# icamlamp_evo.net
KiCad netlist of a schematic drawn in Altium Designer
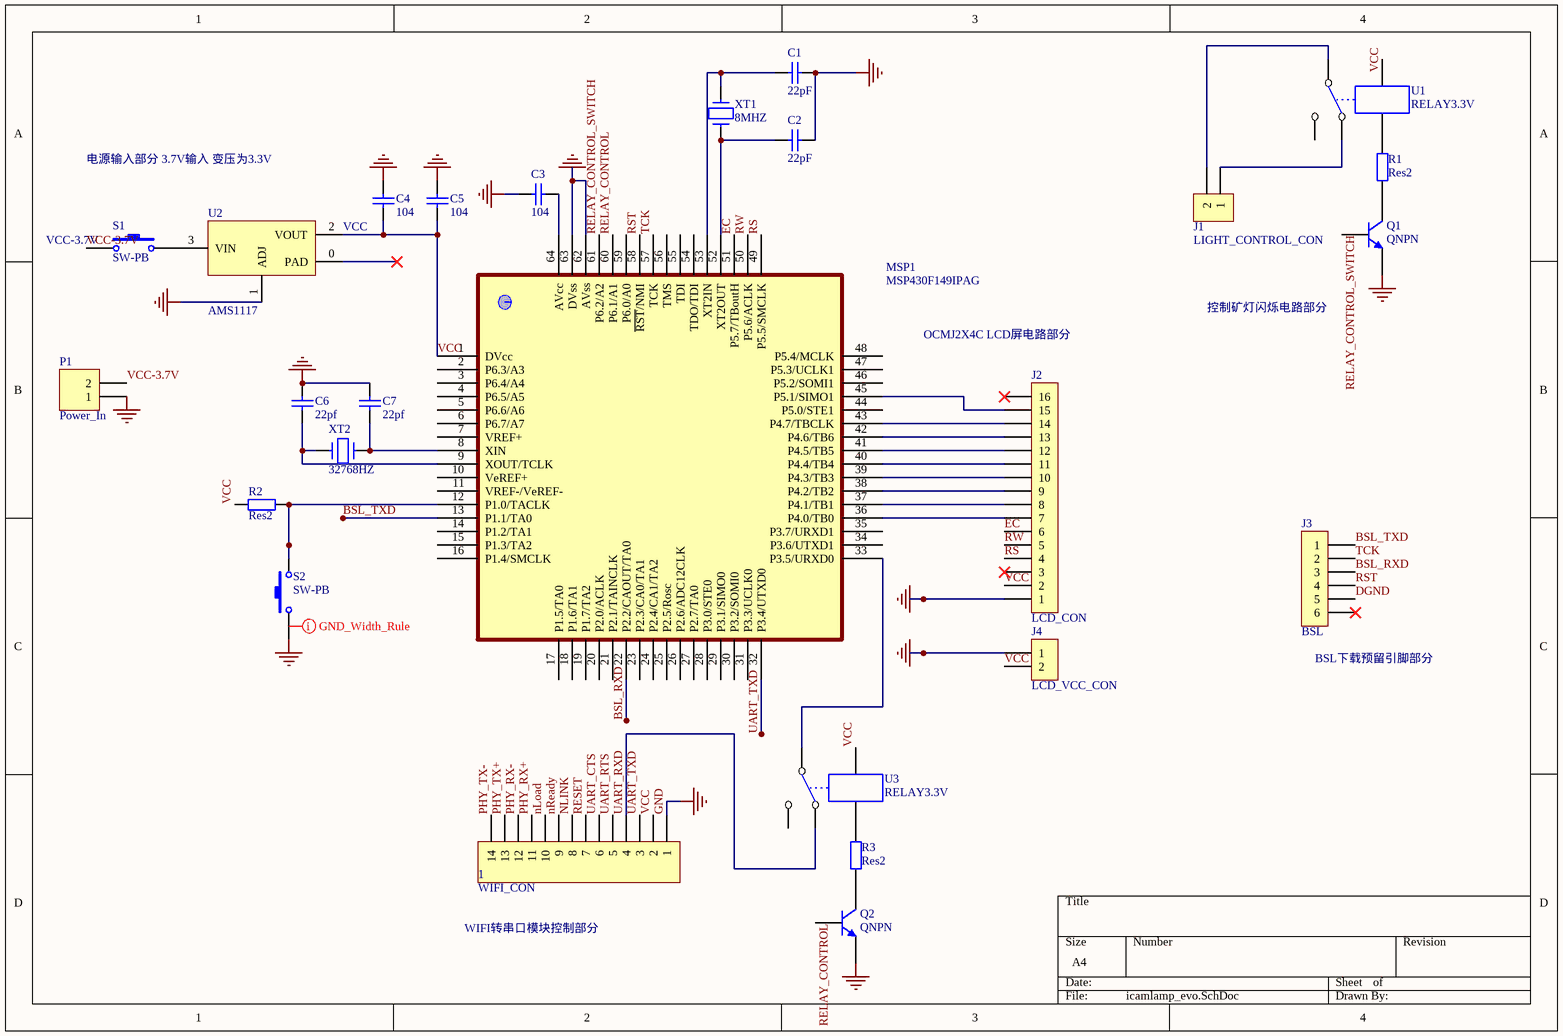
[diagram p0: icamlamp_evo.SchDoc]

(export (version "E")
  (design (tool "Eeschema 10.0.6"))
  (components
    (comp (ref "1") (value "WIFI_CON") (footprint "wificon") (libsource (lib "常用元件库") (part "CON14")))
    (comp (ref "C1")
      (value "22pF")
      (footprint "0805")
      (description "Capacitor")
      (fields (field (name "PUBLISHER") "Altium Limited"))
      (libsource (lib "Miscellaneous Devices") (part "Cap"))
    )
    (comp (ref "C2")
      (value "22pF")
      (footprint "0805")
      (description "Capacitor")
      (fields (field (name "PUBLISHER") "Altium Limited"))
      (libsource (lib "Miscellaneous Devices") (part "Cap"))
    )
    (comp (ref "C3")
      (value "104")
      (footprint "0805")
      (description "Capacitor")
      (fields (field (name "PUBLISHER") "Altium Limited"))
      (libsource (lib "Miscellaneous Devices") (part "Cap"))
    )
    (comp (ref "C4")
      (value "104")
      (footprint "封装库:0805")
      (description "Capacitor")
      (fields (field (name "PUBLISHER") "Altium Limited"))
      (libsource (lib "Miscellaneous Devices") (part "Cap"))
    )
    (comp (ref "C5")
      (value "104")
      (footprint "0805")
      (description "Capacitor")
      (fields (field (name "PUBLISHER") "Altium Limited"))
      (libsource (lib "Miscellaneous Devices") (part "Cap"))
    )
    (comp (ref "C6")
      (value "22pf")
      (footprint "0805")
      (description "Capacitor")
      (fields (field (name "PUBLISHER") "Altium Limited"))
      (libsource (lib "Miscellaneous Devices") (part "Cap"))
    )
    (comp (ref "C7")
      (value "22pf")
      (footprint "0805")
      (description "Capacitor")
      (fields (field (name "PUBLISHER") "Altium Limited"))
      (libsource (lib "Miscellaneous Devices") (part "Cap"))
    )
    (comp (ref "J1") (value "LIGHT_CONTROL_CON") (footprint "SIP2") (libsource (lib "") (part "CON2_1")))
    (comp (ref "J2") (value "LCD_CON") (footprint "HDR2X8") (libsource (lib "元件库") (part "CON16")))
    (comp (ref "J3") (value "BSL") (footprint "HDR2X3") (libsource (lib "常用元件库") (part "CON6")))
    (comp (ref "J4") (value "LCD_VCC_CON") (footprint "SIP2") (libsource (lib "常用元件库") (part "CON2")))
    (comp (ref "MSP1")
      (value "MSP430F149IPAG")
      (footprint "PAG")
      (libsource (lib "MSP430SCH") (part "MSP430F149IPAG"))
    )
    (comp (ref "P1")
      (value "Power_In")
      (footprint "HDR1X2H")
      (description "Header, 2-Pin, Right Angle")
      (fields (field (name "PUBLISHER") "Altium Limited"))
      (libsource (lib "Miscellaneous Connectors") (part "Header 2H"))
    )
    (comp (ref "Q1")
      (value "QNPN")
      (footprint "SO-G3/C2.5")
      (description "NPN Bipolar Transistor")
      (fields (field (name "PUBLISHER") "Altium Limited"))
      (libsource (lib "Miscellaneous Devices") (part "QNPN"))
    )
    (comp (ref "Q2")
      (value "QNPN")
      (footprint "SO-G3/C2.5")
      (description "NPN Bipolar Transistor")
      (fields (field (name "PUBLISHER") "Altium Limited"))
      (libsource (lib "Miscellaneous Devices") (part "QNPN"))
    )
    (comp (ref "R1")
      (value "Res2")
      (footprint "封装库:0805")
      (description "Resistor")
      (fields (field (name "PUBLISHER") "Altium Limited"))
      (libsource (lib "") (part "Res2_1"))
    )
    (comp (ref "R2")
      (value "Res2")
      (footprint "0805")
      (description "Resistor")
      (fields (field (name "PUBLISHER") "Altium Limited"))
      (libsource (lib "Miscellaneous Devices") (part "Res2"))
    )
    (comp (ref "R3")
      (value "Res2")
      (footprint "封装库:0805")
      (description "Resistor")
      (fields (field (name "PUBLISHER") "Altium Limited"))
      (libsource (lib "") (part "Res2_1"))
    )
    (comp (ref "S1")
      (value "SW-PB")
      (footprint "SPST-2")
      (description "Switch")
      (fields (field (name "PUBLISHER") "Altium Limited"))
      (libsource (lib "Miscellaneous Devices") (part "SW-PB"))
    )
    (comp (ref "S2")
      (value "SW-PB")
      (footprint "SPST-2")
      (description "Switch")
      (fields (field (name "PUBLISHER") "Altium Limited"))
      (libsource (lib "Miscellaneous Devices") (part "SW-PB"))
    )
    (comp (ref "U1") (value "RELAY3.3V") (footprint "Relay5V") (libsource (lib "继电器类元件") (part "RELAY5V")))
    (comp (ref "U2")
      (value "AMS1117")
      (footprint "SOT-223")
      (description "LDO ADJ")
      (libsource (lib "元件库") (part "AMS1117"))
    )
    (comp (ref "U3") (value "RELAY3.3V") (footprint "Relay5V") (libsource (lib "继电器类元件") (part "RELAY5V")))
    (comp (ref "XT1")
      (value "8MHZ")
      (footprint "HC-49S")
      (description "CY-49S-8MHZ")
      (libsource (lib "晶振") (part "8MHZ"))
    )
    (comp (ref "XT2")
      (value "32768HZ")
      (footprint "AT26")
      (description "CY-AT26-32768HZ")
      (libsource (lib "晶振") (part "32768HZ"))
    )
  )
  (nets
    (net (code "1") (name "/BSL_RXD") (class "Default")
      (node (ref "J3") (pin "3") (pinfunction "3_3") (pintype "passive"))
      (node (ref "MSP1") (pin "22") (pinfunction "P2.2/CAOUT/TA0_22") (pintype "passive"))
    )
    (net (code "2") (name "/BSL_TXD") (class "Default")
      (node (ref "J3") (pin "1") (pinfunction "1_1") (pintype "passive"))
      (node (ref "MSP1") (pin "13") (pinfunction "P1.1/TA0_13") (pintype "passive"))
    )
    (net (code "3") (name "/DGND") (class "Default")
      (node (ref "J3") (pin "5") (pinfunction "5_5") (pintype "passive"))
    )
    (net (code "4") (name "/EC") (class "Default")
      (node (ref "J2") (pin "6") (pinfunction "6_6") (pintype "passive"))
      (node (ref "MSP1") (pin "51") (pinfunction "P5.7/TBoutH_51") (pintype "passive"))
    )
    (net (code "5") (name "/NLINK") (class "Default")
      (node (ref "1") (pin "8") (pinfunction "8_8") (pintype "passive"))
    )
    (net (code "6") (name "/PHY_RX+") (class "Default")
      (node (ref "1") (pin "11") (pinfunction "11_11") (pintype "passive"))
    )
    (net (code "7") (name "/PHY_RX-") (class "Default")
      (node (ref "1") (pin "12") (pinfunction "12_12") (pintype "passive"))
    )
    (net (code "8") (name "/PHY_TX+") (class "Default")
      (node (ref "1") (pin "13") (pinfunction "13_13") (pintype "passive"))
    )
    (net (code "9") (name "/PHY_TX-") (class "Default")
      (node (ref "1") (pin "14") (pinfunction "14_14") (pintype "passive"))
    )
    (net (code "10") (name "/RELAY_CONTROL") (class "Default")
      (node (ref "MSP1") (pin "60") (pinfunction "P6.1/A1_60") (pintype "passive"))
      (node (ref "Q2") (pin "2") (pinfunction "B_2") (pintype "passive"))
    )
    (net (code "11") (name "/RELAY_CONTROL_SWITCH") (class "Default")
      (node (ref "MSP1") (pin "61") (pinfunction "P6.2/A2_61") (pintype "passive"))
      (node (ref "Q1") (pin "2") (pinfunction "B_2") (pintype "passive"))
    )
    (net (code "12") (name "/RESET") (class "Default")
      (node (ref "1") (pin "7") (pinfunction "7_7") (pintype "passive"))
    )
    (net (code "13") (name "/RS") (class "Default")
      (node (ref "J2") (pin "4") (pinfunction "4_4") (pintype "passive"))
      (node (ref "MSP1") (pin "49") (pinfunction "P5.5/SMCLK_49") (pintype "passive"))
    )
    (net (code "14") (name "/RST") (class "Default")
      (node (ref "J3") (pin "4") (pinfunction "4_4") (pintype "passive"))
      (node (ref "MSP1") (pin "58") (pinfunction "~{RST}/NMI_58") (pintype "passive"))
    )
    (net (code "15") (name "/RW") (class "Default")
      (node (ref "J2") (pin "5") (pinfunction "5_5") (pintype "passive"))
      (node (ref "MSP1") (pin "50") (pinfunction "P5.6/ACLK_50") (pintype "passive"))
    )
    (net (code "16") (name "/TCK") (class "Default")
      (node (ref "J3") (pin "2") (pinfunction "2_2") (pintype "passive"))
      (node (ref "MSP1") (pin "57") (pinfunction "TCK_57") (pintype "passive"))
    )
    (net (code "17") (name "/UART_CTS") (class "Default")
      (node (ref "1") (pin "6") (pinfunction "6_6") (pintype "passive"))
    )
    (net (code "18") (name "/UART_RTS") (class "Default")
      (node (ref "1") (pin "5") (pinfunction "5_5") (pintype "passive"))
    )
    (net (code "19") (name "/UART_RXD") (class "Default")
      (node (ref "1") (pin "4") (pinfunction "4_4") (pintype "passive"))
      (node (ref "U3") (pin "3") (pinfunction "3_3") (pintype "passive"))
    )
    (net (code "20") (name "/UART_TXD") (class "Default")
      (node (ref "1") (pin "3") (pinfunction "3_3") (pintype "passive"))
      (node (ref "MSP1") (pin "32") (pinfunction "P3.4/UTXD0_32") (pintype "passive"))
    )
    (net (code "21") (name "/VCC") (class "Default")
      (node (ref "1") (pin "2") (pinfunction "2_2") (pintype "passive"))
      (node (ref "C4") (pin "2") (pinfunction "2_2") (pintype "passive"))
      (node (ref "C5") (pin "2") (pinfunction "2_2") (pintype "passive"))
      (node (ref "J2") (pin "2") (pinfunction "2_2") (pintype "passive"))
      (node (ref "J4") (pin "2") (pinfunction "2_2") (pintype "passive"))
      (node (ref "MSP1") (pin "1") (pinfunction "DVcc_1") (pintype "passive"))
      (node (ref "R2") (pin "1") (pinfunction "1_1") (pintype "passive"))
      (node (ref "U2") (pin "2") (pinfunction "VOUT_2") (pintype "passive"))
      (node (ref "U3") (pin "4") (pinfunction "4_4") (pintype "passive"))
    )
    (net (code "22") (name "/VCC-3.7V") (class "Default")
      (node (ref "P1") (pin "2") (pinfunction "2_2") (pintype "passive"))
      (node (ref "S1") (pin "1") (pinfunction "1_1") (pintype "passive"))
    )
    (net (code "23") (name "/nLoad") (class "Default")
      (node (ref "1") (pin "10") (pinfunction "10_10") (pintype "passive"))
    )
    (net (code "24") (name "/nReady") (class "Default")
      (node (ref "1") (pin "9") (pinfunction "9_9") (pintype "passive"))
    )
    (net (code "25") (name "GND") (class "Default")
      (node (ref "1") (pin "1") (pinfunction "1_1") (pintype "passive"))
      (node (ref "C1") (pin "1") (pinfunction "1_1") (pintype "passive"))
      (node (ref "C2") (pin "1") (pinfunction "1_1") (pintype "passive"))
      (node (ref "C3") (pin "2") (pinfunction "2_2") (pintype "passive"))
      (node (ref "C4") (pin "1") (pinfunction "1_1") (pintype "passive"))
      (node (ref "C5") (pin "1") (pinfunction "1_1") (pintype "passive"))
      (node (ref "C6") (pin "2") (pinfunction "2_2") (pintype "passive"))
      (node (ref "C7") (pin "2") (pinfunction "2_2") (pintype "passive"))
      (node (ref "J2") (pin "1") (pinfunction "1_1") (pintype "passive"))
      (node (ref "J4") (pin "1") (pinfunction "1_1") (pintype "passive"))
      (node (ref "MSP1") (pin "62") (pinfunction "AVss_62") (pintype "passive"))
      (node (ref "MSP1") (pin "63") (pinfunction "DVss_63") (pintype "passive"))
      (node (ref "P1") (pin "1") (pinfunction "1_1") (pintype "passive"))
      (node (ref "Q1") (pin "3") (pinfunction "E_3") (pintype "passive"))
      (node (ref "Q2") (pin "3") (pinfunction "E_3") (pintype "passive"))
      (node (ref "S2") (pin "1") (pinfunction "1_1") (pintype "passive"))
      (node (ref "U2") (pin "1") (pinfunction "ADJ_1") (pintype "passive"))
    )
    (net (code "26") (name "Net-(J1-Pad1)") (class "Default")
      (node (ref "J1") (pin "1") (pinfunction "1_1") (pintype "passive"))
      (node (ref "U1") (pin "3") (pinfunction "3_3") (pintype "passive"))
    )
    (net (code "27") (name "Net-(J1-Pad2)") (class "Default")
      (node (ref "J1") (pin "2") (pinfunction "2_2") (pintype "passive"))
      (node (ref "U1") (pin "1") (pinfunction "1_1") (pintype "passive"))
    )
    (net (code "28") (name "Net-(MSP1-AVcc)") (class "Default")
      (node (ref "C3") (pin "1") (pinfunction "1_1") (pintype "passive"))
      (node (ref "MSP1") (pin "64") (pinfunction "AVcc_64") (pintype "passive"))
    )
    (net (code "29") (name "Net-(MSP1-P1.0{slash}TACLK)") (class "Default")
      (node (ref "MSP1") (pin "12") (pinfunction "P1.0/TACLK_12") (pintype "passive"))
      (node (ref "R2") (pin "2") (pinfunction "2_2") (pintype "passive"))
      (node (ref "S2") (pin "2") (pinfunction "2_2") (pintype "passive"))
    )
    (net (code "30") (name "Net-(MSP1-P3.5{slash}URXD0)") (class "Default")
      (node (ref "MSP1") (pin "33") (pinfunction "P3.5/URXD0_33") (pintype "passive"))
      (node (ref "U3") (pin "1") (pinfunction "1_1") (pintype "passive"))
    )
    (net (code "31") (name "Net-(MSP1-P4.0{slash}TB0)") (class "Default")
      (node (ref "J2") (pin "7") (pinfunction "7_7") (pintype "passive"))
      (node (ref "MSP1") (pin "36") (pinfunction "P4.0/TB0_36") (pintype "passive"))
    )
    (net (code "32") (name "Net-(MSP1-P4.1{slash}TB1)") (class "Default")
      (node (ref "J2") (pin "8") (pinfunction "8_8") (pintype "passive"))
      (node (ref "MSP1") (pin "37") (pinfunction "P4.1/TB1_37") (pintype "passive"))
    )
    (net (code "33") (name "Net-(MSP1-P4.2{slash}TB2)") (class "Default")
      (node (ref "J2") (pin "9") (pinfunction "9_9") (pintype "passive"))
      (node (ref "MSP1") (pin "38") (pinfunction "P4.2/TB2_38") (pintype "passive"))
    )
    (net (code "34") (name "Net-(MSP1-P4.3{slash}TB3)") (class "Default")
      (node (ref "J2") (pin "10") (pinfunction "10_10") (pintype "passive"))
      (node (ref "MSP1") (pin "39") (pinfunction "P4.3/TB3_39") (pintype "passive"))
    )
    (net (code "35") (name "Net-(MSP1-P4.4{slash}TB4)") (class "Default")
      (node (ref "J2") (pin "11") (pinfunction "11_11") (pintype "passive"))
      (node (ref "MSP1") (pin "40") (pinfunction "P4.4/TB4_40") (pintype "passive"))
    )
    (net (code "36") (name "Net-(MSP1-P4.5{slash}TB5)") (class "Default")
      (node (ref "J2") (pin "12") (pinfunction "12_12") (pintype "passive"))
      (node (ref "MSP1") (pin "41") (pinfunction "P4.5/TB5_41") (pintype "passive"))
    )
    (net (code "37") (name "Net-(MSP1-P4.6{slash}TB6)") (class "Default")
      (node (ref "J2") (pin "13") (pinfunction "13_13") (pintype "passive"))
      (node (ref "MSP1") (pin "42") (pinfunction "P4.6/TB6_42") (pintype "passive"))
    )
    (net (code "38") (name "Net-(MSP1-P4.7{slash}TBCLK)") (class "Default")
      (node (ref "J2") (pin "14") (pinfunction "14_14") (pintype "passive"))
      (node (ref "MSP1") (pin "43") (pinfunction "P4.7/TBCLK_43") (pintype "passive"))
    )
    (net (code "39") (name "Net-(MSP1-P5.1{slash}SIMO1)") (class "Default")
      (node (ref "J2") (pin "15") (pinfunction "15_15") (pintype "passive"))
      (node (ref "MSP1") (pin "45") (pinfunction "P5.1/SIMO1_45") (pintype "passive"))
    )
    (net (code "40") (name "Net-(MSP1-XIN)") (class "Default")
      (node (ref "C7") (pin "1") (pinfunction "1_1") (pintype "passive"))
      (node (ref "MSP1") (pin "8") (pinfunction "XIN_8") (pintype "passive"))
      (node (ref "XT2") (pin "1") (pinfunction "1_1") (pintype "passive"))
    )
    (net (code "41") (name "Net-(MSP1-XOUT{slash}TCLK)") (class "Default")
      (node (ref "C6") (pin "1") (pinfunction "1_1") (pintype "passive"))
      (node (ref "MSP1") (pin "9") (pinfunction "XOUT/TCLK_9") (pintype "passive"))
      (node (ref "XT2") (pin "2") (pinfunction "2_2") (pintype "passive"))
    )
    (net (code "42") (name "Net-(MSP1-XT2IN)") (class "Default")
      (node (ref "C1") (pin "2") (pinfunction "2_2") (pintype "passive"))
      (node (ref "MSP1") (pin "53") (pinfunction "XT2IN_53") (pintype "passive"))
      (node (ref "XT1") (pin "2") (pinfunction "2_2") (pintype "passive"))
    )
    (net (code "43") (name "Net-(MSP1-XT2OUT)") (class "Default")
      (node (ref "C2") (pin "2") (pinfunction "2_2") (pintype "passive"))
      (node (ref "MSP1") (pin "52") (pinfunction "XT2OUT_52") (pintype "passive"))
      (node (ref "XT1") (pin "1") (pinfunction "1_1") (pintype "passive"))
    )
    (net (code "44") (name "Net-(Q1-C)") (class "Default")
      (node (ref "Q1") (pin "1") (pinfunction "C_1") (pintype "passive"))
      (node (ref "R1") (pin "1") (pinfunction "1_1") (pintype "passive"))
    )
    (net (code "45") (name "Net-(Q2-C)") (class "Default")
      (node (ref "Q2") (pin "1") (pinfunction "C_1") (pintype "passive"))
      (node (ref "R3") (pin "1") (pinfunction "1_1") (pintype "passive"))
    )
    (net (code "46") (name "Net-(R1-Pad2)") (class "Default")
      (node (ref "R1") (pin "2") (pinfunction "2_2") (pintype "passive"))
      (node (ref "U1") (pin "5") (pinfunction "5_5") (pintype "passive"))
    )
    (net (code "47") (name "Net-(R3-Pad2)") (class "Default")
      (node (ref "R3") (pin "2") (pinfunction "2_2") (pintype "passive"))
      (node (ref "U3") (pin "5") (pinfunction "5_5") (pintype "passive"))
    )
    (net (code "48") (name "Net-(U2-VIN)") (class "Default")
      (node (ref "S1") (pin "2") (pinfunction "2_2") (pintype "passive"))
      (node (ref "U2") (pin "3") (pinfunction "VIN_3") (pintype "passive"))
    )
    (net (code "49") (name "unconnected-(J2-Pad3)") (class "Default")
      (node (ref "J2") (pin "3") (pinfunction "3_3") (pintype "passive+no_connect"))
    )
    (net (code "50") (name "unconnected-(J2-Pad16)") (class "Default")
      (node (ref "J2") (pin "16") (pinfunction "16_16") (pintype "passive+no_connect"))
    )
    (net (code "51") (name "unconnected-(J3-Pad6)") (class "Default")
      (node (ref "J3") (pin "6") (pinfunction "6_6") (pintype "passive+no_connect"))
    )
    (net (code "52") (name "unconnected-(MSP1-P1.2{slash}TA1-Pad14)") (class "Default")
      (node (ref "MSP1") (pin "14") (pinfunction "P1.2/TA1_14") (pintype "passive"))
    )
    (net (code "53") (name "unconnected-(MSP1-P1.3{slash}TA2-Pad15)") (class "Default")
      (node (ref "MSP1") (pin "15") (pinfunction "P1.3/TA2_15") (pintype "passive"))
    )
    (net (code "54") (name "unconnected-(MSP1-P1.4{slash}SMCLK-Pad16)") (class "Default")
      (node (ref "MSP1") (pin "16") (pinfunction "P1.4/SMCLK_16") (pintype "passive"))
    )
    (net (code "55") (name "unconnected-(MSP1-P1.5{slash}TA0-Pad17)") (class "Default")
      (node (ref "MSP1") (pin "17") (pinfunction "P1.5/TA0_17") (pintype "passive"))
    )
    (net (code "56") (name "unconnected-(MSP1-P1.6{slash}TA1-Pad18)") (class "Default")
      (node (ref "MSP1") (pin "18") (pinfunction "P1.6/TA1_18") (pintype "passive"))
    )
    (net (code "57") (name "unconnected-(MSP1-P1.7{slash}TA2-Pad19)") (class "Default")
      (node (ref "MSP1") (pin "19") (pinfunction "P1.7/TA2_19") (pintype "passive"))
    )
    (net (code "58") (name "unconnected-(MSP1-P2.0{slash}ACLK-Pad20)") (class "Default")
      (node (ref "MSP1") (pin "20") (pinfunction "P2.0/ACLK_20") (pintype "passive"))
    )
    (net (code "59") (name "unconnected-(MSP1-P2.1{slash}TAINCLK-Pad21)") (class "Default")
      (node (ref "MSP1") (pin "21") (pinfunction "P2.1/TAINCLK_21") (pintype "passive"))
    )
    (net (code "60") (name "unconnected-(MSP1-P2.3{slash}CA0{slash}TA1-Pad23)") (class "Default")
      (node (ref "MSP1") (pin "23") (pinfunction "P2.3/CA0/TA1_23") (pintype "passive"))
    )
    (net (code "61") (name "unconnected-(MSP1-P2.4{slash}CA1{slash}TA2-Pad24)") (class "Default")
      (node (ref "MSP1") (pin "24") (pinfunction "P2.4/CA1/TA2_24") (pintype "passive"))
    )
    (net (code "62") (name "unconnected-(MSP1-P2.5{slash}Rosc-Pad25)") (class "Default")
      (node (ref "MSP1") (pin "25") (pinfunction "P2.5/Rosc_25") (pintype "passive"))
    )
    (net (code "63") (name "unconnected-(MSP1-P2.6{slash}ADC12CLK-Pad26)") (class "Default")
      (node (ref "MSP1") (pin "26") (pinfunction "P2.6/ADC12CLK_26") (pintype "passive"))
    )
    (net (code "64") (name "unconnected-(MSP1-P2.7{slash}TA0-Pad27)") (class "Default")
      (node (ref "MSP1") (pin "27") (pinfunction "P2.7/TA0_27") (pintype "passive"))
    )
    (net (code "65") (name "unconnected-(MSP1-P3.0{slash}STE0-Pad28)") (class "Default")
      (node (ref "MSP1") (pin "28") (pinfunction "P3.0/STE0_28") (pintype "passive"))
    )
    (net (code "66") (name "unconnected-(MSP1-P3.1{slash}SIMO0-Pad29)") (class "Default")
      (node (ref "MSP1") (pin "29") (pinfunction "P3.1/SIMO0_29") (pintype "passive"))
    )
    (net (code "67") (name "unconnected-(MSP1-P3.2{slash}SOMI0-Pad30)") (class "Default")
      (node (ref "MSP1") (pin "30") (pinfunction "P3.2/SOMI0_30") (pintype "passive"))
    )
    (net (code "68") (name "unconnected-(MSP1-P3.3{slash}UCLK0-Pad31)") (class "Default")
      (node (ref "MSP1") (pin "31") (pinfunction "P3.3/UCLK0_31") (pintype "passive"))
    )
    (net (code "69") (name "unconnected-(MSP1-P3.6{slash}UTXD1-Pad34)") (class "Default")
      (node (ref "MSP1") (pin "34") (pinfunction "P3.6/UTXD1_34") (pintype "passive"))
    )
    (net (code "70") (name "unconnected-(MSP1-P3.7{slash}URXD1-Pad35)") (class "Default")
      (node (ref "MSP1") (pin "35") (pinfunction "P3.7/URXD1_35") (pintype "passive"))
    )
    (net (code "71") (name "unconnected-(MSP1-P5.0{slash}STE1-Pad44)") (class "Default")
      (node (ref "MSP1") (pin "44") (pinfunction "P5.0/STE1_44") (pintype "passive"))
    )
    (net (code "72") (name "unconnected-(MSP1-P5.2{slash}SOMI1-Pad46)") (class "Default")
      (node (ref "MSP1") (pin "46") (pinfunction "P5.2/SOMI1_46") (pintype "passive"))
    )
    (net (code "73") (name "unconnected-(MSP1-P5.3{slash}UCLK1-Pad47)") (class "Default")
      (node (ref "MSP1") (pin "47") (pinfunction "P5.3/UCLK1_47") (pintype "passive"))
    )
    (net (code "74") (name "unconnected-(MSP1-P5.4{slash}MCLK-Pad48)") (class "Default")
      (node (ref "MSP1") (pin "48") (pinfunction "P5.4/MCLK_48") (pintype "passive"))
    )
    (net (code "75") (name "unconnected-(MSP1-P6.0{slash}A0-Pad59)") (class "Default")
      (node (ref "MSP1") (pin "59") (pinfunction "P6.0/A0_59") (pintype "passive"))
    )
    (net (code "76") (name "unconnected-(MSP1-P6.3{slash}A3-Pad2)") (class "Default")
      (node (ref "MSP1") (pin "2") (pinfunction "P6.3/A3_2") (pintype "passive"))
    )
    (net (code "77") (name "unconnected-(MSP1-P6.4{slash}A4-Pad3)") (class "Default")
      (node (ref "MSP1") (pin "3") (pinfunction "P6.4/A4_3") (pintype "passive"))
    )
    (net (code "78") (name "unconnected-(MSP1-P6.5{slash}A5-Pad4)") (class "Default")
      (node (ref "MSP1") (pin "4") (pinfunction "P6.5/A5_4") (pintype "passive"))
    )
    (net (code "79") (name "unconnected-(MSP1-P6.6{slash}A6-Pad5)") (class "Default")
      (node (ref "MSP1") (pin "5") (pinfunction "P6.6/A6_5") (pintype "passive"))
    )
    (net (code "80") (name "unconnected-(MSP1-P6.7{slash}A7-Pad6)") (class "Default")
      (node (ref "MSP1") (pin "6") (pinfunction "P6.7/A7_6") (pintype "passive"))
    )
    (net (code "81") (name "unconnected-(MSP1-TDI-Pad55)") (class "Default")
      (node (ref "MSP1") (pin "55") (pinfunction "TDI_55") (pintype "passive"))
    )
    (net (code "82") (name "unconnected-(MSP1-TDO{slash}TDI-Pad54)") (class "Default")
      (node (ref "MSP1") (pin "54") (pinfunction "TDO/TDI_54") (pintype "passive"))
    )
    (net (code "83") (name "unconnected-(MSP1-TMS-Pad56)") (class "Default")
      (node (ref "MSP1") (pin "56") (pinfunction "TMS_56") (pintype "passive"))
    )
    (net (code "84") (name "unconnected-(MSP1-VREF+-Pad7)") (class "Default")
      (node (ref "MSP1") (pin "7") (pinfunction "VREF+_7") (pintype "passive"))
    )
    (net (code "85") (name "unconnected-(MSP1-VREF-{slash}VeREF--Pad11)") (class "Default")
      (node (ref "MSP1") (pin "11") (pinfunction "VREF-/VeREF-_11") (pintype "passive"))
    )
    (net (code "86") (name "unconnected-(MSP1-VeREF+-Pad10)") (class "Default")
      (node (ref "MSP1") (pin "10") (pinfunction "VeREF+_10") (pintype "passive"))
    )
    (net (code "87") (name "unconnected-(U1-Pad2)") (class "Default")
      (node (ref "U1") (pin "2") (pinfunction "2_2") (pintype "passive"))
    )
    (net (code "88") (name "unconnected-(U1-Pad4)") (class "Default")
      (node (ref "U1") (pin "4") (pinfunction "4_4") (pintype "passive"))
    )
    (net (code "89") (name "unconnected-(U2-PAD-Pad0)") (class "Default")
      (node (ref "U2") (pin "0") (pinfunction "PAD_0") (pintype "passive+no_connect"))
    )
    (net (code "90") (name "unconnected-(U3-Pad2)") (class "Default")
      (node (ref "U3") (pin "2") (pinfunction "2_2") (pintype "passive"))
    )
  )
)
